# Adapter_MPCIe_to_M2_E.net
KiCad netlist of a schematic drawn in Altium Designer
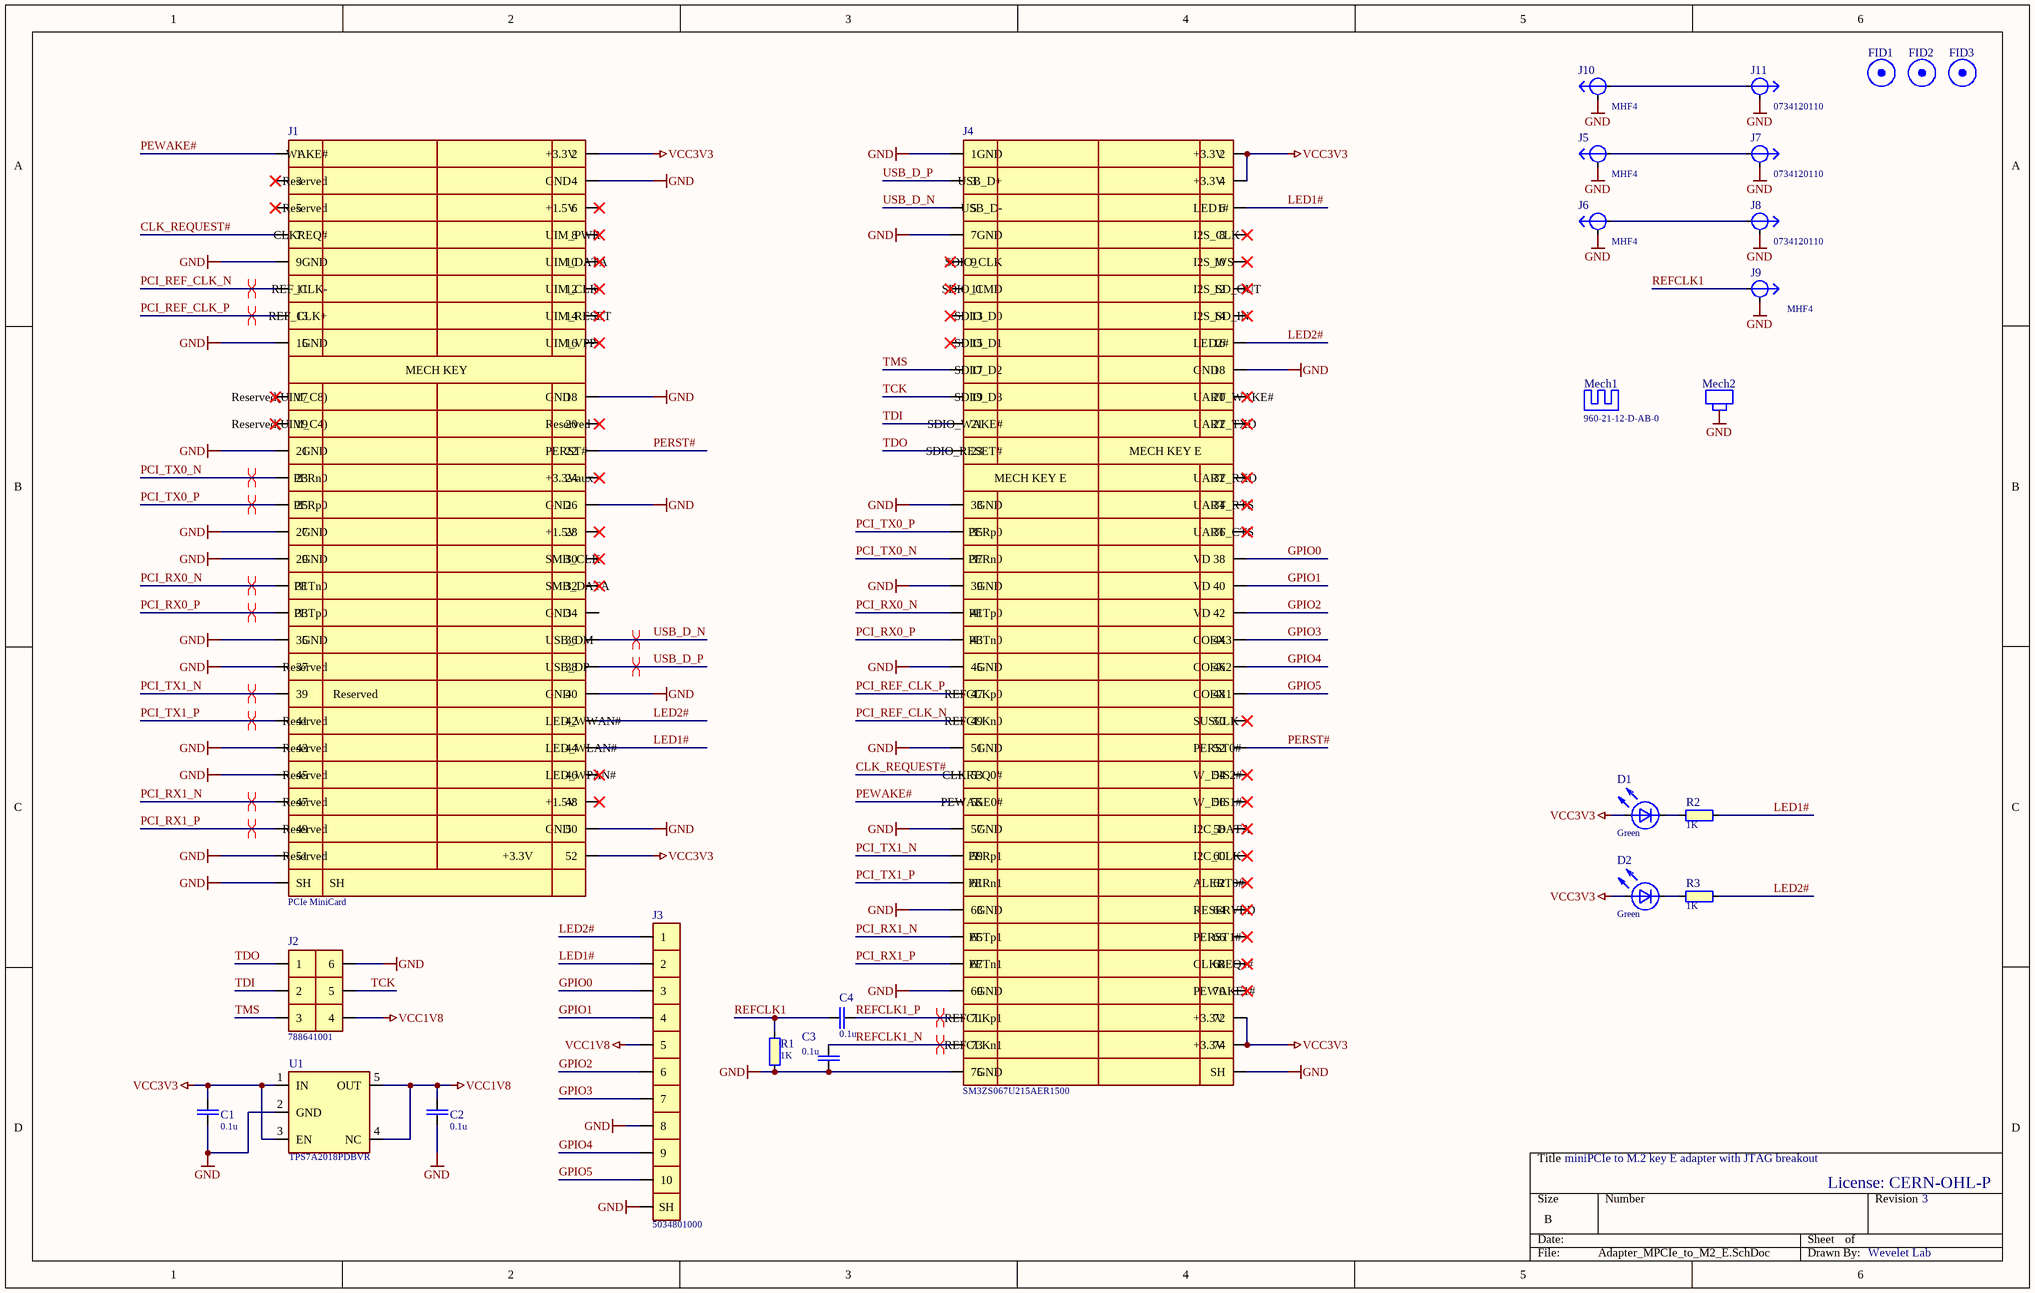
[diagram p0: Adapter_MPCIe_to_M2_E.SchDoc]

(export (version "E")
  (design (tool "Eeschema 10.0.6"))
  (components
    (comp (ref "C1")
      (value "0.1u")
      (footprint "CAPC100X50X55L25N")
      (description "Capacitor, 0.1u, 25V, 10%, X7R, 0402")
      (fields
        (field (name "MANUFACTURER") "Murata Electronics")
        (field (name "Comment") "GRM155R71E104KE14D")
      )
      (libsource (lib "Capacitors") (part "GRM155R71E104KE14D"))
    )
    (comp (ref "C2")
      (value "0.1u")
      (footprint "CAPC100X50X55L25N")
      (description "Capacitor, 0.1u, 25V, 10%, X7R, 0402")
      (fields
        (field (name "MANUFACTURER") "Murata Electronics")
        (field (name "Comment") "GRM155R71E104KE14D")
      )
      (libsource (lib "Capacitors") (part "GRM155R71E104KE14D"))
    )
    (comp (ref "C3")
      (value "0.1u")
      (footprint "CAPC100X50X55L25N")
      (description "Capacitor, 0.1u, 25V, 10%, X7R, 0402")
      (fields
        (field (name "MANUFACTURER") "Murata Electronics")
        (field (name "Comment") "GRM155R71E104KE14D")
      )
      (libsource (lib "Capacitors") (part "GRM155R71E104KE14D"))
    )
    (comp (ref "C4")
      (value "0.1u")
      (footprint "CAPC100X50X55L25N")
      (description "Capacitor, 0.1u, 25V, 10%, X7R, 0402")
      (fields
        (field (name "MANUFACTURER") "Murata Electronics")
        (field (name "Comment") "GRM155R71E104KE14D")
      )
      (libsource (lib "Capacitors") (part "GRM155R71E104KE14D"))
    )
    (comp (ref "D1")
      (value "Green")
      (footprint "LEDC160X80X80L40N-Green")
      (description "LED Diode, Green, -30/+85, SMD0603")
      (fields (field (name "MANUFACTURER") "Lite-On Inc.") (field (name "Comment") "LTST-C190KGKT"))
      (libsource (lib "Diode_Transistor") (part "LTST-C190KGKT"))
    )
    (comp (ref "D2")
      (value "Green")
      (footprint "LEDC160X80X80L40N-Green")
      (description "LED Diode, Green, -30/+85, SMD0603")
      (fields (field (name "MANUFACTURER") "Lite-On Inc.") (field (name "Comment") "LTST-C190KGKT"))
      (libsource (lib "Diode_Transistor") (part "LTST-C190KGKT"))
    )
    (comp (ref "FID1")
      (value "Fiducial")
      (footprint "Fiducial_2D")
      (libsource (lib "Mech") (part "Fiducial"))
    )
    (comp (ref "FID2")
      (value "Fiducial")
      (footprint "Fiducial_2D")
      (libsource (lib "Mech") (part "Fiducial"))
    )
    (comp (ref "FID3")
      (value "Fiducial")
      (footprint "Fiducial_2D")
      (libsource (lib "Mech") (part "Fiducial"))
    )
    (comp (ref "J1")
      (value "PCIe MiniCard")
      (footprint "EDGE_CONN_PCIe_MiniCard")
      (description "Edge connector PCIe MiniCard")
      (libsource (lib "Connectors") (part "Edge connector PCIe MiniCard"))
    )
    (comp (ref "J2")
      (value "788641001")
      (footprint "Molex_788641001_Mating")
      (description "Conn, Mating, 788641001")
      (fields (field (name "MANUFACTURER") "Molex") (field (name "Comment") "788641001_Mating"))
      (libsource (lib "Connectors") (part "788641001_Mating"))
    )
    (comp (ref "J3")
      (value "5034801000")
      (footprint "MOLEX_5034801000")
      (description "Conn, FFC, 10 pins, 0.5mm, -40/+85, Right, SMD")
      (fields (field (name "MANUFACTURER") "Molex"))
      (libsource (lib "Connectors") (part "5034801000"))
    )
    (comp (ref "J4")
      (value "SM3ZS067U215AER1500")
      (footprint "JAE_SM3ZS067U215AER1500")
      (description "Conn M.2, Key E, -40/+80, SMD")
      (fields (field (name "MANUFACTURER") "JAE"))
      (libsource (lib "Connectors") (part "SM3ZS067U215AER1500"))
    )
    (comp (ref "J5")
      (value "MHF4")
      (footprint "LINX_CONMHF4-SMD-G-T")
      (description "Conn, IPEX MHF4, Male Pin, 50 Ohm, -65/+165, SMD")
      (fields
        (field (name "MANUFACTURER") "Linx Technologies Inc.")
        (field (name "Comment") "CONMHF4-SMD-G-T")
      )
      (libsource (lib "Connectors") (part "CONMHF4-SMD-G-T"))
    )
    (comp (ref "J6")
      (value "MHF4")
      (footprint "LINX_CONMHF4-SMD-G-T")
      (description "Conn, IPEX MHF4, Male Pin, 50 Ohm, -65/+165, SMD")
      (fields
        (field (name "MANUFACTURER") "Linx Technologies Inc.")
        (field (name "Comment") "CONMHF4-SMD-G-T")
      )
      (libsource (lib "Connectors") (part "CONMHF4-SMD-G-T"))
    )
    (comp (ref "J7")
      (value "0734120110")
      (footprint "MOLEX_734120110")
      (description "Conn, U.FL (UMCC), Male Pin, 50 Ohm, -40/+90, SMD")
      (fields (field (name "MANUFACTURER") "Molex"))
      (libsource (lib "Connectors") (part "0734120110"))
    )
    (comp (ref "J8")
      (value "0734120110")
      (footprint "MOLEX_734120110")
      (description "Conn, U.FL (UMCC), Male Pin, 50 Ohm, -40/+90, SMD")
      (fields (field (name "MANUFACTURER") "Molex"))
      (libsource (lib "Connectors") (part "0734120110"))
    )
    (comp (ref "J9")
      (value "MHF4")
      (footprint "LINX_CONMHF4-SMD-G-T")
      (description "Conn, IPEX MHF4, Male Pin, 50 Ohm, -65/+165, SMD")
      (fields
        (field (name "MANUFACTURER") "Linx Technologies Inc.")
        (field (name "Comment") "CONMHF4-SMD-G-T")
      )
      (libsource (lib "Connectors") (part "CONMHF4-SMD-G-T"))
    )
    (comp (ref "J10")
      (value "MHF4")
      (footprint "LINX_CONMHF4-SMD-G-T")
      (description "Conn, IPEX MHF4, Male Pin, 50 Ohm, -65/+165, SMD")
      (fields
        (field (name "MANUFACTURER") "Linx Technologies Inc.")
        (field (name "Comment") "CONMHF4-SMD-G-T")
      )
      (libsource (lib "Connectors") (part "CONMHF4-SMD-G-T"))
    )
    (comp (ref "J11")
      (value "0734120110")
      (footprint "MOLEX_734120110")
      (description "Conn, U.FL (UMCC), Male Pin, 50 Ohm, -40/+90, SMD")
      (fields (field (name "MANUFACTURER") "Molex"))
      (libsource (lib "Connectors") (part "0734120110"))
    )
    (comp (ref "Mech1")
      (value "960-21-12-D-AB-0")
      (footprint "WAKEFIELD_960-21-12-D-AB-0")
      (description "Mech, Heatsink, 21x12 mm, front, push pins")
      (fields (field (name "MANUFACTURER") "Wakefield"))
      (libsource (lib "Mech") (part "960-21-12-D-AB-0"))
    )
    (comp (ref "Mech2")
      (value "SM3ZS067U215-NUT1-R2500")
      (footprint "JAE_SM3ZS067U215-NUT1")
      (description "Mech, standoff, M2, 0.35 mm")
      (fields (field (name "MANUFACTURER") "JAE"))
      (libsource (lib "Mech") (part "SM3ZS067U215-NUT1-R2500"))
    )
    (comp (ref "R1")
      (value "1K")
      (footprint "RESC100X50X40L20N")
      (description "Resistor, 1K, 0.063W, 5%, 0402")
      (fields (field (name "Comment") "Res-0402-1K-5%"))
      (libsource (lib "Resistors") (part "Res-0402-1K-5%"))
    )
    (comp (ref "R2")
      (value "1K")
      (footprint "RESC100X50X40L20N")
      (description "Resistor, 1K, 0.063W, 5%, 0402")
      (fields (field (name "Comment") "Res-0402-1K-5%"))
      (libsource (lib "") (part "Res-0402-1K-5%_1"))
    )
    (comp (ref "R3")
      (value "1K")
      (footprint "RESC100X50X40L20N")
      (description "Resistor, 1K, 0.063W, 5%, 0402")
      (fields (field (name "Comment") "Res-0402-1K-5%"))
      (libsource (lib "") (part "Res-0402-1K-5%_1"))
    )
    (comp (ref "U1")
      (value "TPS7A2018PDBVR")
      (footprint "SOT23-5P95_280X145L45X40N")
      (description "IC, VolReg, DC/DC, 2.2/5.5V, 1.8V, 0.25A, -40/+125, 4-X2SON")
      (fields (field (name "MANUFACTURER") "Texas Instruments"))
      (libsource (lib "MyLibrary") (part "TPS7A2018PDBVR"))
    )
  )
  (nets
    (net (code "1") (name "/CLK_REQUEST#") (class "Default")
      (node (ref "J1") (pin "7") (pinfunction "7_7") (pintype "passive"))
      (node (ref "J4") (pin "53") (pinfunction "53_53") (pintype "passive"))
    )
    (net (code "2") (name "/GPIO0") (class "Default")
      (node (ref "J3") (pin "3") (pinfunction "3_3") (pintype "passive"))
      (node (ref "J4") (pin "38") (pinfunction "38_38") (pintype "passive"))
    )
    (net (code "3") (name "/GPIO1") (class "Default")
      (node (ref "J3") (pin "4") (pinfunction "4_4") (pintype "passive"))
      (node (ref "J4") (pin "40") (pinfunction "40_40") (pintype "passive"))
    )
    (net (code "4") (name "/GPIO2") (class "Default")
      (node (ref "J3") (pin "6") (pinfunction "6_6") (pintype "passive"))
      (node (ref "J4") (pin "42") (pinfunction "42_42") (pintype "passive"))
    )
    (net (code "5") (name "/GPIO3") (class "Default")
      (node (ref "J3") (pin "7") (pinfunction "7_7") (pintype "passive"))
      (node (ref "J4") (pin "44") (pinfunction "44_44") (pintype "passive"))
    )
    (net (code "6") (name "/GPIO4") (class "Default")
      (node (ref "J3") (pin "9") (pinfunction "9_9") (pintype "passive"))
      (node (ref "J4") (pin "46") (pinfunction "46_46") (pintype "passive"))
    )
    (net (code "7") (name "/GPIO5") (class "Default")
      (node (ref "J3") (pin "10") (pinfunction "10_10") (pintype "passive"))
      (node (ref "J4") (pin "48") (pinfunction "48_48") (pintype "passive"))
    )
    (net (code "8") (name "/LED1#") (class "Default")
      (node (ref "J1") (pin "44") (pinfunction "44_44") (pintype "passive"))
      (node (ref "J3") (pin "2") (pinfunction "2_2") (pintype "passive"))
      (node (ref "J4") (pin "6") (pinfunction "6_6") (pintype "passive"))
      (node (ref "R2") (pin "1") (pinfunction "1_1") (pintype "passive"))
    )
    (net (code "9") (name "/LED2#") (class "Default")
      (node (ref "J1") (pin "42") (pinfunction "42_42") (pintype "passive"))
      (node (ref "J3") (pin "1") (pinfunction "1_1") (pintype "passive"))
      (node (ref "J4") (pin "16") (pinfunction "16_16") (pintype "passive"))
      (node (ref "R3") (pin "1") (pinfunction "1_1") (pintype "passive"))
    )
    (net (code "10") (name "/PCI_REF_CLK_N") (class "Default")
      (node (ref "J1") (pin "11") (pinfunction "11_11") (pintype "passive"))
      (node (ref "J4") (pin "49") (pinfunction "49_49") (pintype "passive"))
    )
    (net (code "11") (name "/PCI_REF_CLK_P") (class "Default")
      (node (ref "J1") (pin "13") (pinfunction "13_13") (pintype "passive"))
      (node (ref "J4") (pin "47") (pinfunction "47_47") (pintype "passive"))
    )
    (net (code "12") (name "/PCI_RX0_N") (class "Default")
      (node (ref "J1") (pin "31") (pinfunction "31_31") (pintype "passive"))
      (node (ref "J4") (pin "41") (pinfunction "41_41") (pintype "passive"))
    )
    (net (code "13") (name "/PCI_RX0_P") (class "Default")
      (node (ref "J1") (pin "33") (pinfunction "33_33") (pintype "passive"))
      (node (ref "J4") (pin "43") (pinfunction "43_43") (pintype "passive"))
    )
    (net (code "14") (name "/PCI_RX1_N") (class "Default")
      (node (ref "J1") (pin "47") (pinfunction "47_47") (pintype "passive"))
      (node (ref "J4") (pin "65") (pinfunction "65_65") (pintype "passive"))
    )
    (net (code "15") (name "/PCI_RX1_P") (class "Default")
      (node (ref "J1") (pin "49") (pinfunction "49_49") (pintype "passive"))
      (node (ref "J4") (pin "67") (pinfunction "67_67") (pintype "passive"))
    )
    (net (code "16") (name "/PCI_TX0_N") (class "Default")
      (node (ref "J1") (pin "23") (pinfunction "23_23") (pintype "passive"))
      (node (ref "J4") (pin "37") (pinfunction "37_37") (pintype "passive"))
    )
    (net (code "17") (name "/PCI_TX0_P") (class "Default")
      (node (ref "J1") (pin "25") (pinfunction "25_25") (pintype "passive"))
      (node (ref "J4") (pin "35") (pinfunction "35_35") (pintype "passive"))
    )
    (net (code "18") (name "/PCI_TX1_N") (class "Default")
      (node (ref "J1") (pin "39") (pinfunction "39_39") (pintype "passive"))
      (node (ref "J4") (pin "59") (pinfunction "59_59") (pintype "passive"))
    )
    (net (code "19") (name "/PCI_TX1_P") (class "Default")
      (node (ref "J1") (pin "41") (pinfunction "41_41") (pintype "passive"))
      (node (ref "J4") (pin "61") (pinfunction "61_61") (pintype "passive"))
    )
    (net (code "20") (name "/PERST#") (class "Default")
      (node (ref "J1") (pin "22") (pinfunction "22_22") (pintype "passive"))
      (node (ref "J4") (pin "52") (pinfunction "52_52") (pintype "passive"))
    )
    (net (code "21") (name "/PEWAKE#") (class "Default")
      (node (ref "J1") (pin "1") (pinfunction "1_1") (pintype "passive"))
      (node (ref "J4") (pin "55") (pinfunction "55_55") (pintype "passive"))
    )
    (net (code "22") (name "/REFCLK1") (class "Default")
      (node (ref "C4") (pin "1") (pinfunction "1_1") (pintype "passive"))
      (node (ref "J9") (pin "1") (pinfunction "1_1") (pintype "passive"))
      (node (ref "R1") (pin "1") (pinfunction "1_1") (pintype "passive"))
    )
    (net (code "23") (name "/REFCLK1_N") (class "Default")
      (node (ref "C3") (pin "2") (pinfunction "2_2") (pintype "passive"))
      (node (ref "J4") (pin "73") (pinfunction "73_73") (pintype "passive"))
    )
    (net (code "24") (name "/REFCLK1_P") (class "Default")
      (node (ref "C4") (pin "2") (pinfunction "2_2") (pintype "passive"))
      (node (ref "J4") (pin "71") (pinfunction "71_71") (pintype "passive"))
    )
    (net (code "25") (name "/TCK") (class "Default")
      (node (ref "J2") (pin "5") (pinfunction "5_5") (pintype "passive"))
      (node (ref "J4") (pin "19") (pinfunction "19_19") (pintype "passive"))
    )
    (net (code "26") (name "/TDI") (class "Default")
      (node (ref "J2") (pin "2") (pinfunction "2_2") (pintype "passive"))
      (node (ref "J4") (pin "21") (pinfunction "21_21") (pintype "passive"))
    )
    (net (code "27") (name "/TDO") (class "Default")
      (node (ref "J2") (pin "1") (pinfunction "1_1") (pintype "passive"))
      (node (ref "J4") (pin "23") (pinfunction "23_23") (pintype "passive"))
    )
    (net (code "28") (name "/TMS") (class "Default")
      (node (ref "J2") (pin "3") (pinfunction "3_3") (pintype "passive"))
      (node (ref "J4") (pin "17") (pinfunction "17_17") (pintype "passive"))
    )
    (net (code "29") (name "/USB_D_N") (class "Default")
      (node (ref "J1") (pin "36") (pinfunction "36_36") (pintype "passive"))
      (node (ref "J4") (pin "5") (pinfunction "5_5") (pintype "passive"))
    )
    (net (code "30") (name "/USB_D_P") (class "Default")
      (node (ref "J1") (pin "38") (pinfunction "38_38") (pintype "passive"))
      (node (ref "J4") (pin "3") (pinfunction "3_3") (pintype "passive"))
    )
    (net (code "31") (name "GND") (class "Default")
      (node (ref "C1") (pin "1") (pinfunction "1_1") (pintype "passive"))
      (node (ref "C2") (pin "1") (pinfunction "1_1") (pintype "passive"))
      (node (ref "C3") (pin "1") (pinfunction "1_1") (pintype "passive"))
      (node (ref "J1") (pin "15") (pinfunction "15_15") (pintype "passive"))
      (node (ref "J1") (pin "18") (pinfunction "18_18") (pintype "passive"))
      (node (ref "J1") (pin "21") (pinfunction "21_21") (pintype "passive"))
      (node (ref "J1") (pin "26") (pinfunction "26_26") (pintype "passive"))
      (node (ref "J1") (pin "27") (pinfunction "27_27") (pintype "passive"))
      (node (ref "J1") (pin "29") (pinfunction "29_29") (pintype "passive"))
      (node (ref "J1") (pin "35") (pinfunction "35_35") (pintype "passive"))
      (node (ref "J1") (pin "37") (pinfunction "37_37") (pintype "passive"))
      (node (ref "J1") (pin "4") (pinfunction "4_4") (pintype "passive"))
      (node (ref "J1") (pin "40") (pinfunction "40_40") (pintype "passive"))
      (node (ref "J1") (pin "43") (pinfunction "43_43") (pintype "passive"))
      (node (ref "J1") (pin "45") (pinfunction "45_45") (pintype "passive"))
      (node (ref "J1") (pin "50") (pinfunction "50_50") (pintype "passive"))
      (node (ref "J1") (pin "51") (pinfunction "51_51") (pintype "passive"))
      (node (ref "J1") (pin "9") (pinfunction "9_9") (pintype "passive"))
      (node (ref "J1") (pin "SH") (pinfunction "SH_SH") (pintype "passive"))
      (node (ref "J10") (pin "SH") (pinfunction "SH_SH") (pintype "passive"))
      (node (ref "J11") (pin "SH") (pinfunction "SH_SH") (pintype "passive"))
      (node (ref "J2") (pin "6") (pinfunction "6_6") (pintype "passive"))
      (node (ref "J3") (pin "8") (pinfunction "8_8") (pintype "passive"))
      (node (ref "J3") (pin "SH") (pinfunction "SH_SH") (pintype "passive"))
      (node (ref "J4") (pin "1") (pinfunction "1_1") (pintype "passive"))
      (node (ref "J4") (pin "18") (pinfunction "18_18") (pintype "passive"))
      (node (ref "J4") (pin "33") (pinfunction "33_33") (pintype "passive"))
      (node (ref "J4") (pin "39") (pinfunction "39_39") (pintype "passive"))
      (node (ref "J4") (pin "45") (pinfunction "45_45") (pintype "passive"))
      (node (ref "J4") (pin "51") (pinfunction "51_51") (pintype "passive"))
      (node (ref "J4") (pin "57") (pinfunction "57_57") (pintype "passive"))
      (node (ref "J4") (pin "63") (pinfunction "63_63") (pintype "passive"))
      (node (ref "J4") (pin "69") (pinfunction "69_69") (pintype "passive"))
      (node (ref "J4") (pin "7") (pinfunction "7_7") (pintype "passive"))
      (node (ref "J4") (pin "75") (pinfunction "75_75") (pintype "passive"))
      (node (ref "J4") (pin "SH") (pinfunction "SH_SH") (pintype "passive"))
      (node (ref "J5") (pin "SH") (pinfunction "SH_SH") (pintype "passive"))
      (node (ref "J6") (pin "SH") (pinfunction "SH_SH") (pintype "passive"))
      (node (ref "J7") (pin "SH") (pinfunction "SH_SH") (pintype "passive"))
      (node (ref "J8") (pin "SH") (pinfunction "SH_SH") (pintype "passive"))
      (node (ref "J9") (pin "SH") (pinfunction "SH_SH") (pintype "passive"))
      (node (ref "Mech2") (pin "SH") (pinfunction "SH_SH") (pintype "passive"))
      (node (ref "R1") (pin "2") (pinfunction "2_2") (pintype "passive"))
      (node (ref "U1") (pin "2") (pinfunction "GND_2") (pintype "passive"))
    )
    (net (code "32") (name "Net-(D1-PadC)") (class "Default")
      (node (ref "D1") (pin "C") (pinfunction "C_C") (pintype "passive"))
      (node (ref "R2") (pin "2") (pinfunction "2_2") (pintype "passive"))
    )
    (net (code "33") (name "Net-(D2-PadC)") (class "Default")
      (node (ref "D2") (pin "C") (pinfunction "C_C") (pintype "passive"))
      (node (ref "R3") (pin "2") (pinfunction "2_2") (pintype "passive"))
    )
    (net (code "34") (name "Net-(J5-Pad1)") (class "Default")
      (node (ref "J5") (pin "1") (pinfunction "1_1") (pintype "passive"))
      (node (ref "J7") (pin "1") (pinfunction "1_1") (pintype "passive"))
    )
    (net (code "35") (name "Net-(J6-Pad1)") (class "Default")
      (node (ref "J6") (pin "1") (pinfunction "1_1") (pintype "passive"))
      (node (ref "J8") (pin "1") (pinfunction "1_1") (pintype "passive"))
    )
    (net (code "36") (name "Net-(J10-Pad1)") (class "Default")
      (node (ref "J10") (pin "1") (pinfunction "1_1") (pintype "passive"))
      (node (ref "J11") (pin "1") (pinfunction "1_1") (pintype "passive"))
    )
    (net (code "37") (name "VCC1V8") (class "Default")
      (node (ref "C2") (pin "2") (pinfunction "2_2") (pintype "passive"))
      (node (ref "J2") (pin "4") (pinfunction "4_4") (pintype "passive"))
      (node (ref "J3") (pin "5") (pinfunction "5_5") (pintype "passive"))
      (node (ref "U1") (pin "4") (pinfunction "NC_4") (pintype "passive"))
      (node (ref "U1") (pin "5") (pinfunction "OUT_5") (pintype "passive"))
    )
    (net (code "38") (name "VCC3V3") (class "Default")
      (node (ref "C1") (pin "2") (pinfunction "2_2") (pintype "passive"))
      (node (ref "D1") (pin "A") (pinfunction "A_A") (pintype "passive"))
      (node (ref "D2") (pin "A") (pinfunction "A_A") (pintype "passive"))
      (node (ref "J1") (pin "2") (pinfunction "2_2") (pintype "passive"))
      (node (ref "J1") (pin "52") (pinfunction "52_52") (pintype "passive"))
      (node (ref "J4") (pin "2") (pinfunction "2_2") (pintype "passive"))
      (node (ref "J4") (pin "4") (pinfunction "4_4") (pintype "passive"))
      (node (ref "J4") (pin "72") (pinfunction "72_72") (pintype "passive"))
      (node (ref "J4") (pin "74") (pinfunction "74_74") (pintype "passive"))
      (node (ref "U1") (pin "1") (pinfunction "IN_1") (pintype "passive"))
      (node (ref "U1") (pin "3") (pinfunction "EN_3") (pintype "passive"))
    )
    (net (code "39") (name "unconnected-(J1-Pad3)") (class "Default")
      (node (ref "J1") (pin "3") (pinfunction "3_3") (pintype "passive+no_connect"))
    )
    (net (code "40") (name "unconnected-(J1-Pad5)") (class "Default")
      (node (ref "J1") (pin "5") (pinfunction "5_5") (pintype "passive+no_connect"))
    )
    (net (code "41") (name "unconnected-(J1-Pad6)") (class "Default")
      (node (ref "J1") (pin "6") (pinfunction "6_6") (pintype "passive+no_connect"))
    )
    (net (code "42") (name "unconnected-(J1-Pad8)") (class "Default")
      (node (ref "J1") (pin "8") (pinfunction "8_8") (pintype "passive+no_connect"))
    )
    (net (code "43") (name "unconnected-(J1-Pad10)") (class "Default")
      (node (ref "J1") (pin "10") (pinfunction "10_10") (pintype "passive+no_connect"))
    )
    (net (code "44") (name "unconnected-(J1-Pad12)") (class "Default")
      (node (ref "J1") (pin "12") (pinfunction "12_12") (pintype "passive+no_connect"))
    )
    (net (code "45") (name "unconnected-(J1-Pad14)") (class "Default")
      (node (ref "J1") (pin "14") (pinfunction "14_14") (pintype "passive+no_connect"))
    )
    (net (code "46") (name "unconnected-(J1-Pad16)") (class "Default")
      (node (ref "J1") (pin "16") (pinfunction "16_16") (pintype "passive+no_connect"))
    )
    (net (code "47") (name "unconnected-(J1-Pad17)") (class "Default")
      (node (ref "J1") (pin "17") (pinfunction "17_17") (pintype "passive+no_connect"))
    )
    (net (code "48") (name "unconnected-(J1-Pad19)") (class "Default")
      (node (ref "J1") (pin "19") (pinfunction "19_19") (pintype "passive+no_connect"))
    )
    (net (code "49") (name "unconnected-(J1-Pad20)") (class "Default")
      (node (ref "J1") (pin "20") (pinfunction "20_20") (pintype "passive+no_connect"))
    )
    (net (code "50") (name "unconnected-(J1-Pad24)") (class "Default")
      (node (ref "J1") (pin "24") (pinfunction "24_24") (pintype "passive+no_connect"))
    )
    (net (code "51") (name "unconnected-(J1-Pad28)") (class "Default")
      (node (ref "J1") (pin "28") (pinfunction "28_28") (pintype "passive+no_connect"))
    )
    (net (code "52") (name "unconnected-(J1-Pad30)") (class "Default")
      (node (ref "J1") (pin "30") (pinfunction "30_30") (pintype "passive+no_connect"))
    )
    (net (code "53") (name "unconnected-(J1-Pad32)") (class "Default")
      (node (ref "J1") (pin "32") (pinfunction "32_32") (pintype "passive+no_connect"))
    )
    (net (code "54") (name "unconnected-(J1-Pad34)") (class "Default")
      (node (ref "J1") (pin "34") (pinfunction "34_34") (pintype "passive"))
    )
    (net (code "55") (name "unconnected-(J1-Pad46)") (class "Default")
      (node (ref "J1") (pin "46") (pinfunction "46_46") (pintype "passive+no_connect"))
    )
    (net (code "56") (name "unconnected-(J1-Pad48)") (class "Default")
      (node (ref "J1") (pin "48") (pinfunction "48_48") (pintype "passive+no_connect"))
    )
    (net (code "57") (name "unconnected-(J4-Pad8)") (class "Default")
      (node (ref "J4") (pin "8") (pinfunction "8_8") (pintype "passive+no_connect"))
    )
    (net (code "58") (name "unconnected-(J4-Pad9)") (class "Default")
      (node (ref "J4") (pin "9") (pinfunction "9_9") (pintype "passive+no_connect"))
    )
    (net (code "59") (name "unconnected-(J4-Pad10)") (class "Default")
      (node (ref "J4") (pin "10") (pinfunction "10_10") (pintype "passive+no_connect"))
    )
    (net (code "60") (name "unconnected-(J4-Pad11)") (class "Default")
      (node (ref "J4") (pin "11") (pinfunction "11_11") (pintype "passive+no_connect"))
    )
    (net (code "61") (name "unconnected-(J4-Pad12)") (class "Default")
      (node (ref "J4") (pin "12") (pinfunction "12_12") (pintype "passive+no_connect"))
    )
    (net (code "62") (name "unconnected-(J4-Pad13)") (class "Default")
      (node (ref "J4") (pin "13") (pinfunction "13_13") (pintype "passive+no_connect"))
    )
    (net (code "63") (name "unconnected-(J4-Pad14)") (class "Default")
      (node (ref "J4") (pin "14") (pinfunction "14_14") (pintype "passive+no_connect"))
    )
    (net (code "64") (name "unconnected-(J4-Pad15)") (class "Default")
      (node (ref "J4") (pin "15") (pinfunction "15_15") (pintype "passive+no_connect"))
    )
    (net (code "65") (name "unconnected-(J4-Pad20)") (class "Default")
      (node (ref "J4") (pin "20") (pinfunction "20_20") (pintype "passive+no_connect"))
    )
    (net (code "66") (name "unconnected-(J4-Pad22)") (class "Default")
      (node (ref "J4") (pin "22") (pinfunction "22_22") (pintype "passive+no_connect"))
    )
    (net (code "67") (name "unconnected-(J4-Pad32)") (class "Default")
      (node (ref "J4") (pin "32") (pinfunction "32_32") (pintype "passive+no_connect"))
    )
    (net (code "68") (name "unconnected-(J4-Pad34)") (class "Default")
      (node (ref "J4") (pin "34") (pinfunction "34_34") (pintype "passive+no_connect"))
    )
    (net (code "69") (name "unconnected-(J4-Pad36)") (class "Default")
      (node (ref "J4") (pin "36") (pinfunction "36_36") (pintype "passive+no_connect"))
    )
    (net (code "70") (name "unconnected-(J4-Pad50)") (class "Default")
      (node (ref "J4") (pin "50") (pinfunction "50_50") (pintype "passive+no_connect"))
    )
    (net (code "71") (name "unconnected-(J4-Pad54)") (class "Default")
      (node (ref "J4") (pin "54") (pinfunction "54_54") (pintype "passive+no_connect"))
    )
    (net (code "72") (name "unconnected-(J4-Pad56)") (class "Default")
      (node (ref "J4") (pin "56") (pinfunction "56_56") (pintype "passive+no_connect"))
    )
    (net (code "73") (name "unconnected-(J4-Pad58)") (class "Default")
      (node (ref "J4") (pin "58") (pinfunction "58_58") (pintype "passive+no_connect"))
    )
    (net (code "74") (name "unconnected-(J4-Pad60)") (class "Default")
      (node (ref "J4") (pin "60") (pinfunction "60_60") (pintype "passive+no_connect"))
    )
    (net (code "75") (name "unconnected-(J4-Pad62)") (class "Default")
      (node (ref "J4") (pin "62") (pinfunction "62_62") (pintype "passive+no_connect"))
    )
    (net (code "76") (name "unconnected-(J4-Pad64)") (class "Default")
      (node (ref "J4") (pin "64") (pinfunction "64_64") (pintype "passive+no_connect"))
    )
    (net (code "77") (name "unconnected-(J4-Pad66)") (class "Default")
      (node (ref "J4") (pin "66") (pinfunction "66_66") (pintype "passive+no_connect"))
    )
    (net (code "78") (name "unconnected-(J4-Pad68)") (class "Default")
      (node (ref "J4") (pin "68") (pinfunction "68_68") (pintype "passive+no_connect"))
    )
    (net (code "79") (name "unconnected-(J4-Pad70)") (class "Default")
      (node (ref "J4") (pin "70") (pinfunction "70_70") (pintype "passive+no_connect"))
    )
    (net (code "80") (name "unconnected-(Mech1-PadMH)") (class "Default")
      (node (ref "Mech1") (pin "MH") (pinfunction "MH_MH") (pintype "passive"))
    )
  )
)
